# Water_level_Detector.net
KiCad netlist of a schematic drawn in EAGLE
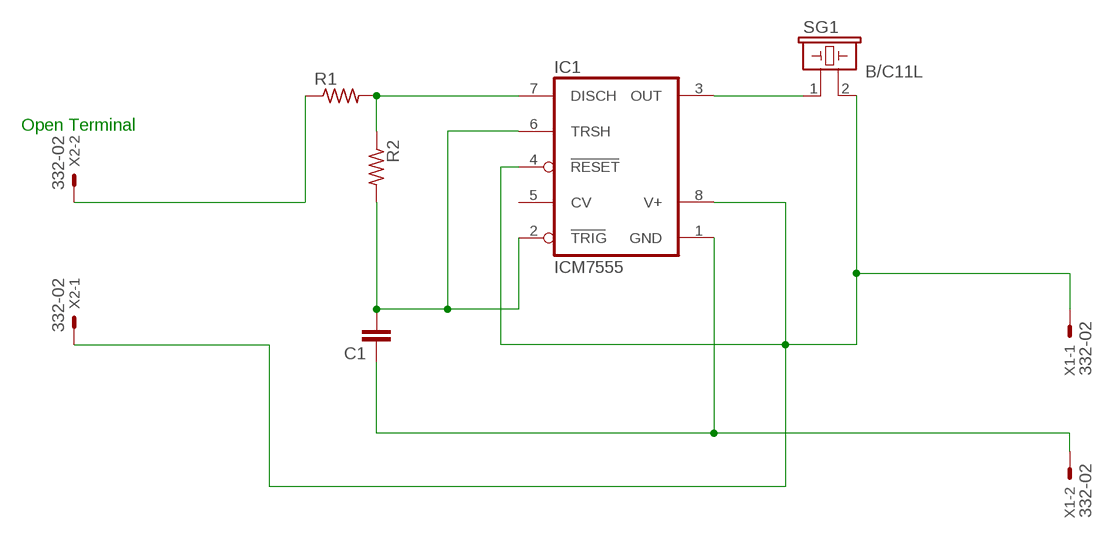
[diagram p0: schematic, sheet 1]

(export (version "E")
  (design (tool "Eeschema 10.0.6"))
  (components
    (comp (ref "C1")
      (value "C5/2.5")
      (footprint "eagle-import:C5B2.5")
      (libsource (lib "eagle-import") (part "C5/2.5"))
    )
    (comp (ref "IC1")
      (value "ICM7555")
      (footprint "eagle-import:DIL08")
      (fields (field (name "MF") "MAXIM") (field (name "MPN") "ICM7555IPA+"))
      (libsource (lib "eagle-import") (part "ICM7555"))
    )
    (comp (ref "R1")
      (value "R-US_0204/7")
      (footprint "eagle-import:0204_7")
      (libsource (lib "eagle-import") (part "R-US_0204/7"))
    )
    (comp (ref "R2")
      (value "R-US_0204/7")
      (footprint "eagle-import:0204_7")
      (libsource (lib "eagle-import") (part "R-US_0204/7"))
    )
    (comp (ref "SG1")
      (value "B/C11L")
      (footprint "eagle-import:B_C11L")
      (libsource (lib "eagle-import") (part "B/C11L"))
    )
    (comp (ref "X1")
      (value "332-02")
      (footprint "eagle-import:332-02")
      (libsource (lib "eagle-import") (part "332-02"))
    )
    (comp (ref "X2")
      (value "332-02")
      (footprint "eagle-import:332-02")
      (libsource (lib "eagle-import") (part "332-02"))
    )
  )
  (nets
    (net (code "1") (name "Net-(IC1-DISCH)") (class "Default")
      (node (ref "IC1") (pin "7") (pinfunction "DISCH_7") (pintype "input"))
      (node (ref "R1") (pin "2") (pinfunction "2_2") (pintype "passive"))
      (node (ref "R2") (pin "1") (pinfunction "1_1") (pintype "passive"))
    )
    (net (code "2") (name "Net-(IC1-GND)") (class "Default")
      (node (ref "C1") (pin "1") (pinfunction "1_1") (pintype "passive"))
      (node (ref "IC1") (pin "1") (pinfunction "GND_1") (pintype "power_in"))
      (node (ref "X1") (pin "2") (pinfunction "S_2") (pintype "passive"))
    )
    (net (code "3") (name "Net-(IC1-OUT)") (class "Default")
      (node (ref "IC1") (pin "3") (pinfunction "OUT_3") (pintype "output"))
      (node (ref "SG1") (pin "1") (pinfunction "1_1") (pintype "passive"))
    )
    (net (code "4") (name "Net-(IC1-RESET)") (class "Default")
      (node (ref "IC1") (pin "4") (pinfunction "RESET_4") (pintype "input"))
      (node (ref "IC1") (pin "8") (pinfunction "V+_8") (pintype "power_in"))
      (node (ref "SG1") (pin "2") (pinfunction "2_2") (pintype "passive"))
      (node (ref "X1") (pin "1") (pinfunction "S_1") (pintype "passive"))
      (node (ref "X2") (pin "1") (pinfunction "S_1") (pintype "passive"))
    )
    (net (code "5") (name "Net-(IC1-TRIG)") (class "Default")
      (node (ref "C1") (pin "2") (pinfunction "2_2") (pintype "passive"))
      (node (ref "IC1") (pin "2") (pinfunction "TRIG_2") (pintype "bidirectional"))
      (node (ref "IC1") (pin "6") (pinfunction "TRSH_6") (pintype "input"))
      (node (ref "R2") (pin "2") (pinfunction "2_2") (pintype "passive"))
    )
    (net (code "6") (name "Net-(X2B-S)") (class "Default")
      (node (ref "R1") (pin "1") (pinfunction "1_1") (pintype "passive"))
      (node (ref "X2") (pin "2") (pinfunction "S_2") (pintype "passive"))
    )
    (net (code "7") (name "unconnected-(IC1-CV-Pad5)") (class "Default")
      (node (ref "IC1") (pin "5") (pinfunction "CV_5") (pintype "passive"))
    )
  )
)
